# led_boost_test.net
KiCad netlist of a schematic drawn in EAGLE
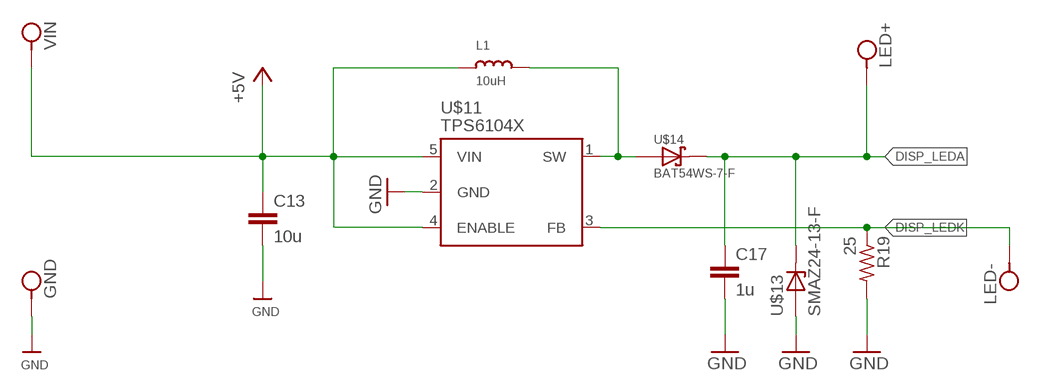
[diagram p0: schematic, sheet 1]

(export (version "E")
  (design (tool "Eeschema 10.0.6"))
  (components
    (comp (ref "C13")
      (value "10u")
      (footprint "eagle-import:C0805K")
      (libsource (lib "eagle-import") (part "C-EUC0805K"))
    )
    (comp (ref "C17")
      (value "1u")
      (footprint "eagle-import:C0805K")
      (libsource (lib "eagle-import") (part "C-EUC0805K"))
    )
    (comp (ref "GND")
      (value "MOTOR_PAD")
      (footprint "eagle-import:MOTOR_PAD")
      (libsource (lib "eagle-import") (part "MOTOR_PAD"))
    )
    (comp (ref "L1")
      (value "10uH")
      (footprint "eagle-import:INDUCTOR_5X5MM_NR5040_NOTHERMALS")
      (libsource (lib "eagle-import") (part "INDUCTORNR5040"))
    )
    (comp (ref "LED+")
      (value "MOTOR_PAD")
      (footprint "eagle-import:MOTOR_PAD")
      (libsource (lib "eagle-import") (part "MOTOR_PAD"))
    )
    (comp (ref "LED-")
      (value "MOTOR_PAD")
      (footprint "eagle-import:MOTOR_PAD")
      (libsource (lib "eagle-import") (part "MOTOR_PAD"))
    )
    (comp (ref "R19")
      (value "25")
      (footprint "eagle-import:R0805")
      (libsource (lib "eagle-import") (part "R-US_R0805"))
    )
    (comp (ref "U$11")
      (value "TPS6104X")
      (footprint "eagle-import:SOT23-5L")
      (libsource (lib "eagle-import") (part "TPS6104X"))
    )
    (comp (ref "U$13")
      (value "SMAZ24-13-F")
      (footprint "eagle-import:SMA_DIODE")
      (libsource (lib "eagle-import") (part "SMAZ24-13-F"))
    )
    (comp (ref "U$14")
      (value "BAT54WS-7-F")
      (footprint "eagle-import:SOD323")
      (libsource (lib "eagle-import") (part "BAT54WS-7-F"))
    )
    (comp (ref "VIN")
      (value "MOTOR_PAD")
      (footprint "eagle-import:MOTOR_PAD")
      (libsource (lib "eagle-import") (part "MOTOR_PAD"))
    )
  )
  (nets
    (net (code "1") (name "+5V") (class "Default")
      (node (ref "C13") (pin "1") (pinfunction "1_1") (pintype "passive"))
      (node (ref "L1") (pin "P$1") (pinfunction "1_P$1") (pintype "passive"))
      (node (ref "U$11") (pin "4") (pinfunction "ENABLE_4") (pintype "bidirectional"))
      (node (ref "U$11") (pin "5") (pinfunction "VIN_5") (pintype "bidirectional"))
      (node (ref "VIN") (pin "P$1") (pinfunction "P$1_P$1") (pintype "bidirectional"))
    )
    (net (code "2") (name "DISP_LEDA") (class "Default")
      (node (ref "C17") (pin "1") (pinfunction "1_1") (pintype "passive"))
      (node (ref "LED+") (pin "P$1") (pinfunction "P$1_P$1") (pintype "bidirectional"))
      (node (ref "U$13") (pin "C") (pinfunction "C_C") (pintype "bidirectional"))
      (node (ref "U$14") (pin "1") (pinfunction "C_1") (pintype "bidirectional"))
    )
    (net (code "3") (name "DISP_LEDK") (class "Default")
      (node (ref "LED-") (pin "P$1") (pinfunction "P$1_P$1") (pintype "bidirectional"))
      (node (ref "R19") (pin "1") (pinfunction "1_1") (pintype "passive"))
      (node (ref "U$11") (pin "3") (pinfunction "FB_3") (pintype "bidirectional"))
    )
    (net (code "4") (name "GND") (class "Default")
      (node (ref "C13") (pin "2") (pinfunction "2_2") (pintype "passive"))
      (node (ref "C17") (pin "2") (pinfunction "2_2") (pintype "passive"))
      (node (ref "GND") (pin "P$1") (pinfunction "P$1_P$1") (pintype "bidirectional"))
      (node (ref "R19") (pin "2") (pinfunction "2_2") (pintype "passive"))
      (node (ref "U$11") (pin "2") (pinfunction "GND_2") (pintype "bidirectional"))
      (node (ref "U$13") (pin "A") (pinfunction "A_A") (pintype "input"))
    )
    (net (code "5") (name "Net-(L1-2)") (class "Default")
      (node (ref "L1") (pin "P$2") (pinfunction "2_P$2") (pintype "passive"))
      (node (ref "U$11") (pin "1") (pinfunction "SW_1") (pintype "bidirectional"))
      (node (ref "U$14") (pin "2") (pinfunction "A_2") (pintype "bidirectional"))
    )
  )
)
